# Street_Fighter_v1_0.net
KiCad netlist of a schematic drawn in EAGLE
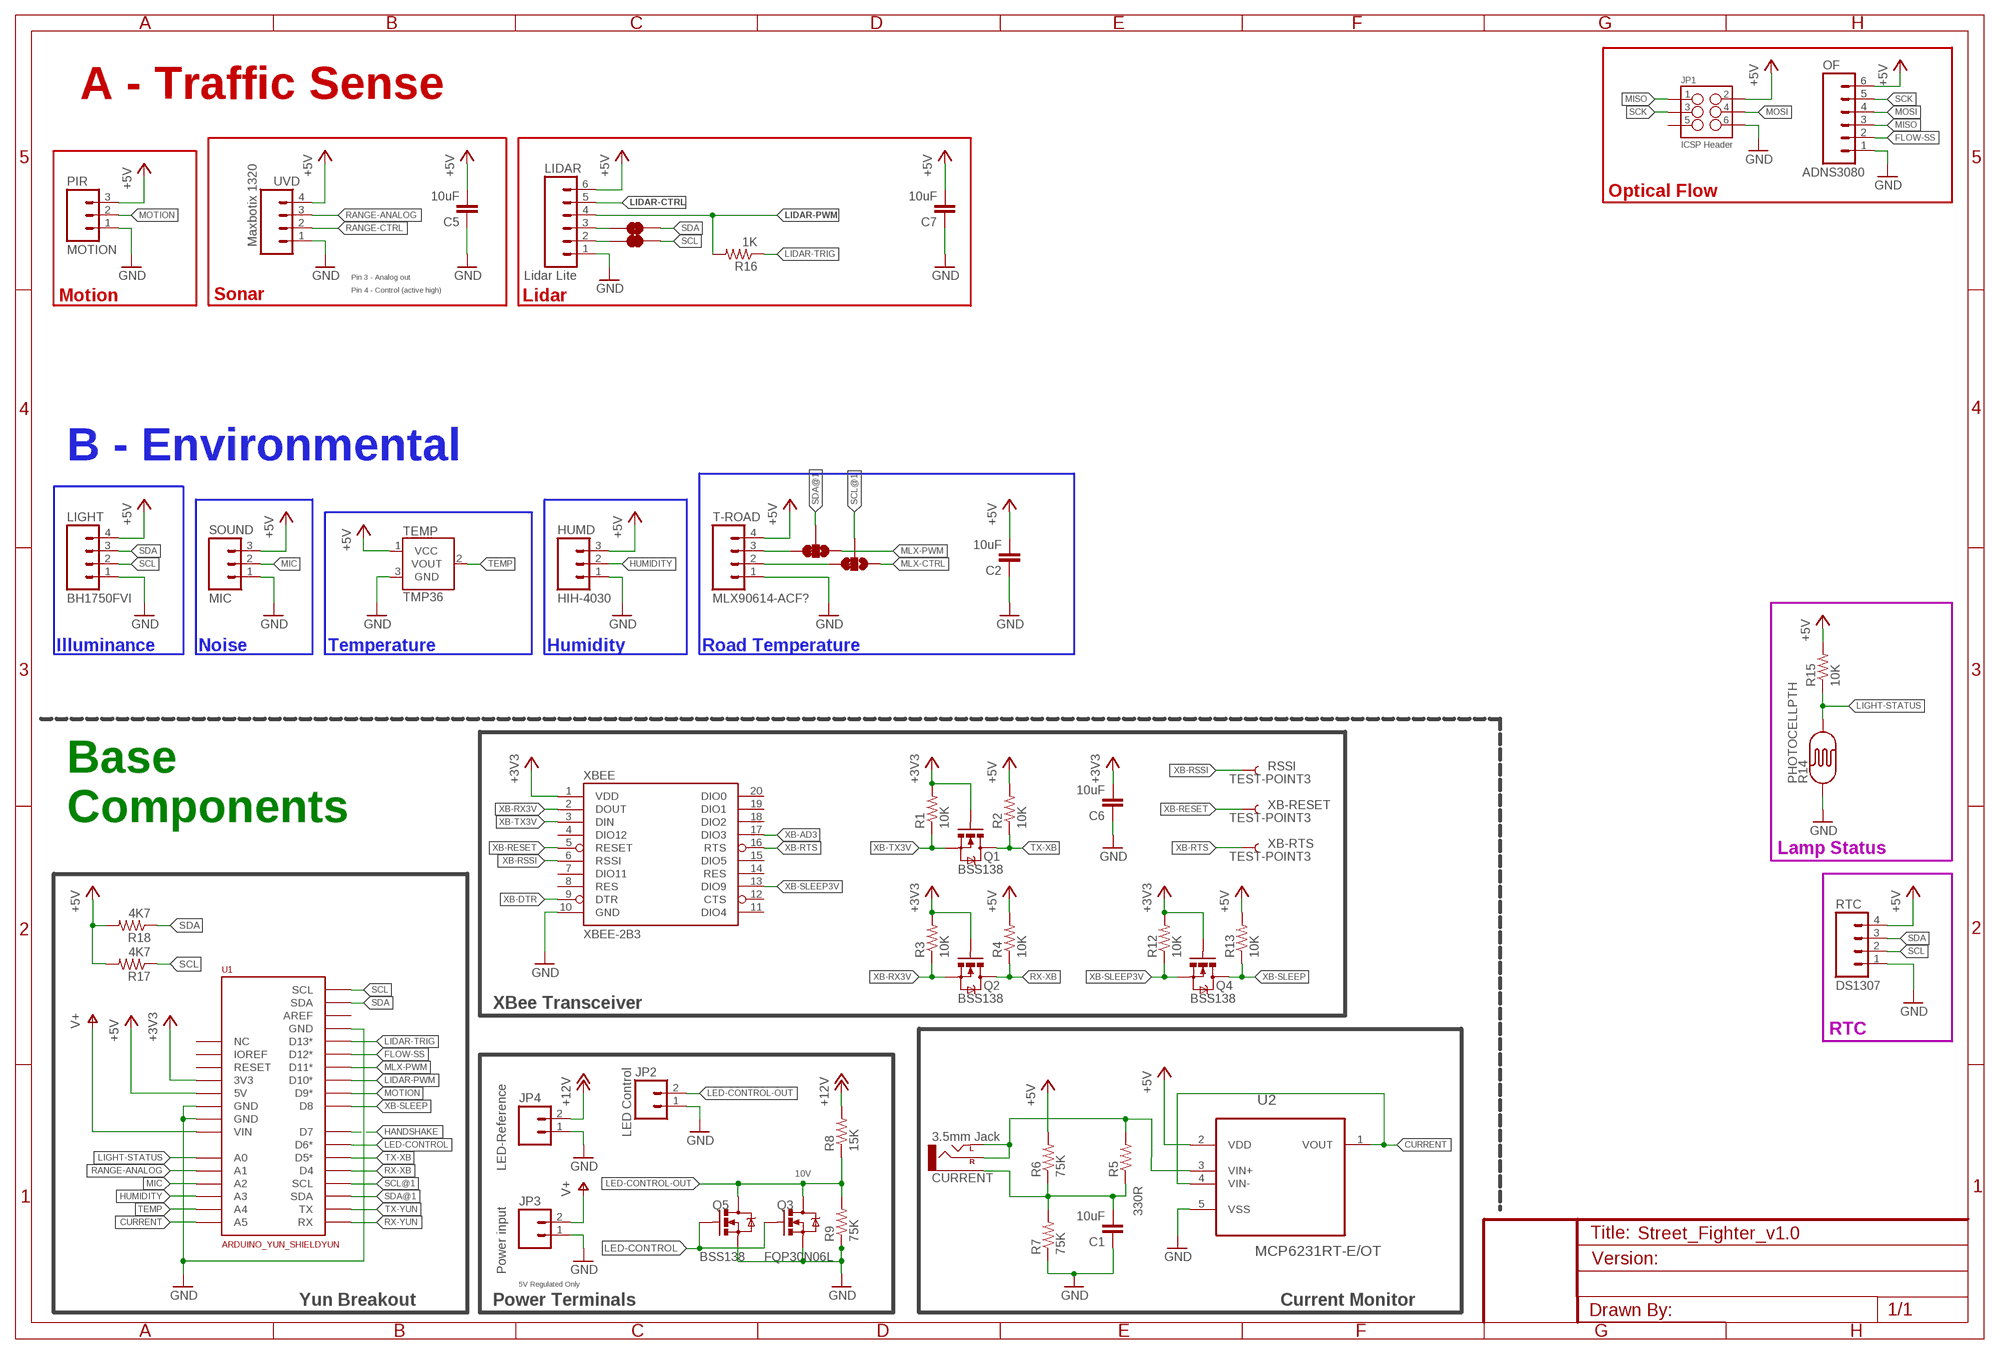
[diagram p0: schematic, sheet 1]

(export (version "E")
  (design (tool "Eeschema 10.0.6"))
  (components
    (comp (ref "C1")
      (value "10uF")
      (footprint "eagle-import:1206")
      (libsource (lib "eagle-import") (part "10UF-6.3V-20%(1206)"))
    )
    (comp (ref "C2")
      (value "10uF")
      (footprint "eagle-import:1206")
      (libsource (lib "eagle-import") (part "10UF-6.3V-20%(1206)"))
    )
    (comp (ref "C5")
      (value "10uF")
      (footprint "eagle-import:1206")
      (libsource (lib "eagle-import") (part "10UF-6.3V-20%(1206)"))
    )
    (comp (ref "C6")
      (value "10uF")
      (footprint "eagle-import:1206")
      (libsource (lib "eagle-import") (part "10UF-6.3V-20%(1206)"))
    )
    (comp (ref "C7")
      (value "10uF")
      (footprint "eagle-import:1206")
      (libsource (lib "eagle-import") (part "10UF-6.3V-20%(1206)"))
    )
    (comp (ref "CURRENT")
      (value "3.5mm Jack")
      (footprint "eagle-import:AUDIO-JACK")
      (libsource (lib "eagle-import") (part "AUDIO-JACKPTH"))
    )
    (comp (ref "HUMD")
      (value "HIH-4030")
      (footprint "eagle-import:1X03")
      (libsource (lib "eagle-import") (part "M03PTH"))
    )
    (comp (ref "JP1")
      (value "ICSP Header")
      (footprint "eagle-import:2X3")
      (libsource (lib "eagle-import") (part "M03X22X3_SILK_SM"))
    )
    (comp (ref "JP2")
      (value "LED Control")
      (footprint "eagle-import:1X02_LONGPADS")
      (libsource (lib "eagle-import") (part "M02PTH3"))
    )
    (comp (ref "JP3")
      (value "Power input")
      (footprint "eagle-import:1X02_LONGPADS")
      (libsource (lib "eagle-import") (part "M02PTH3"))
    )
    (comp (ref "JP4")
      (value "LED-Reference")
      (footprint "eagle-import:1X02_LONGPADS")
      (libsource (lib "eagle-import") (part "M02PTH3"))
    )
    (comp (ref "LIDAR")
      (value "Lidar Lite")
      (footprint "eagle-import:1X06")
      (libsource (lib "eagle-import") (part "M06SIP"))
    )
    (comp (ref "LIGHT")
      (value "BH1750FVI")
      (footprint "eagle-import:1X04")
      (libsource (lib "eagle-import") (part "M04PTH"))
    )
    (comp (ref "OF")
      (value "ADNS3080")
      (footprint "eagle-import:1X06")
      (libsource (lib "eagle-import") (part "M06SIP"))
    )
    (comp (ref "PIR")
      (value "MOTION")
      (footprint "eagle-import:1X03")
      (libsource (lib "eagle-import") (part "M03PTH"))
    )
    (comp (ref "Q1")
      (value "BSS138")
      (footprint "eagle-import:SOT23")
      (libsource (lib "eagle-import") (part "MOSFET-NCHANNELBSS123LT1G"))
    )
    (comp (ref "Q2")
      (value "BSS138")
      (footprint "eagle-import:SOT23")
      (libsource (lib "eagle-import") (part "MOSFET-NCHANNELBSS123LT1G"))
    )
    (comp (ref "Q3")
      (value "FQP30N06L")
      (footprint "eagle-import:TO220V")
      (libsource (lib "eagle-import") (part "MOSFET-NCHANNELFQP30N06L"))
    )
    (comp (ref "Q4")
      (value "BSS138")
      (footprint "eagle-import:SOT23")
      (libsource (lib "eagle-import") (part "MOSFET-NCHANNELBSS123LT1G"))
    )
    (comp (ref "Q5")
      (value "BSS138")
      (footprint "eagle-import:SOT23")
      (libsource (lib "eagle-import") (part "MOSFET-NCHANNELBSS123LT1G"))
    )
    (comp (ref "R1")
      (value "10K")
      (footprint "eagle-import:1206")
      (libsource (lib "eagle-import") (part "RESISTOR1206"))
    )
    (comp (ref "R2")
      (value "10K")
      (footprint "eagle-import:1206")
      (libsource (lib "eagle-import") (part "RESISTOR1206"))
    )
    (comp (ref "R3")
      (value "10K")
      (footprint "eagle-import:1206")
      (libsource (lib "eagle-import") (part "RESISTOR1206"))
    )
    (comp (ref "R4")
      (value "10K")
      (footprint "eagle-import:1206")
      (libsource (lib "eagle-import") (part "RESISTOR1206"))
    )
    (comp (ref "R5")
      (value "330R")
      (footprint "eagle-import:1206")
      (libsource (lib "eagle-import") (part "RESISTOR1206"))
    )
    (comp (ref "R6")
      (value "75K")
      (footprint "eagle-import:1206")
      (libsource (lib "eagle-import") (part "RESISTOR1206"))
    )
    (comp (ref "R7")
      (value "75K")
      (footprint "eagle-import:1206")
      (libsource (lib "eagle-import") (part "RESISTOR1206"))
    )
    (comp (ref "R8")
      (value "15K")
      (footprint "eagle-import:1206")
      (libsource (lib "eagle-import") (part "RESISTOR1206"))
    )
    (comp (ref "R9")
      (value "75K")
      (footprint "eagle-import:1206")
      (libsource (lib "eagle-import") (part "RESISTOR1206"))
    )
    (comp (ref "R12")
      (value "10K")
      (footprint "eagle-import:1206")
      (libsource (lib "eagle-import") (part "RESISTOR1206"))
    )
    (comp (ref "R13")
      (value "10K")
      (footprint "eagle-import:1206")
      (libsource (lib "eagle-import") (part "RESISTOR1206"))
    )
    (comp (ref "R14")
      (value "PHOTOCELLPTH")
      (footprint "eagle-import:PHOTOCELL")
      (libsource (lib "eagle-import") (part "PHOTOCELLPTH"))
    )
    (comp (ref "R15")
      (value "10K")
      (footprint "eagle-import:1206")
      (libsource (lib "eagle-import") (part "RESISTOR1206"))
    )
    (comp (ref "R16")
      (value "1K")
      (footprint "eagle-import:1206")
      (libsource (lib "eagle-import") (part "RESISTOR1206"))
    )
    (comp (ref "R17")
      (value "4K7")
      (footprint "eagle-import:1206")
      (libsource (lib "eagle-import") (part "RESISTOR1206"))
    )
    (comp (ref "R18")
      (value "4K7")
      (footprint "eagle-import:1206")
      (libsource (lib "eagle-import") (part "RESISTOR1206"))
    )
    (comp (ref "RSSI")
      (value "TEST-POINT3")
      (footprint "eagle-import:PAD.03X.03")
      (libsource (lib "eagle-import") (part "TEST-POINT3"))
    )
    (comp (ref "RTC")
      (value "DS1307")
      (footprint "eagle-import:1X04")
      (libsource (lib "eagle-import") (part "M04PTH"))
    )
    (comp (ref "SJ1")
      (value "JUMPER-PAD-2-NC_BY_TRACE")
      (footprint "eagle-import:PAD-JUMPER-2-NC_BY_TRACE_YES_SILK")
      (libsource (lib "eagle-import") (part "JUMPER-PAD-2-NC_BY_TRACE"))
    )
    (comp (ref "SJ2")
      (value "JUMPER-PAD-2-NC_BY_TRACE")
      (footprint "eagle-import:PAD-JUMPER-2-NC_BY_TRACE_YES_SILK")
      (libsource (lib "eagle-import") (part "JUMPER-PAD-2-NC_BY_TRACE"))
    )
    (comp (ref "SJ3")
      (value "JUMPER-PAD-3-2OF3_NC_BY_TRACE_SMALL")
      (footprint "eagle-import:PAD-JUMPER-3-2OF3_NC_BY_TRACE_YES_SILK_FULL_BOX")
      (libsource (lib "eagle-import") (part "JUMPER-PAD-3-2OF3_NC_BY_TRACE_SMALL"))
    )
    (comp (ref "SJ4")
      (value "JUMPER-PAD-3-2OF3_NC_BY_TRACE_SMALL")
      (footprint "eagle-import:PAD-JUMPER-3-2OF3_NC_BY_TRACE_YES_SILK_FULL_BOX")
      (libsource (lib "eagle-import") (part "JUMPER-PAD-3-2OF3_NC_BY_TRACE_SMALL"))
    )
    (comp (ref "SOUND")
      (value "MIC")
      (footprint "eagle-import:1X03")
      (libsource (lib "eagle-import") (part "M03PTH"))
    )
    (comp (ref "T-ROAD")
      (value "MLX90614-ACF?")
      (footprint "eagle-import:1X04")
      (libsource (lib "eagle-import") (part "M04PTH"))
    )
    (comp (ref "TEMP")
      (value "TMP36")
      (footprint "eagle-import:TO-92")
      (libsource (lib "eagle-import") (part "TMP36GT9"))
    )
    (comp (ref "U1")
      (value "ARDUINO_YUN_SHIELDYUN")
      (footprint "eagle-import:DUEMILANOVE_VIAS")
      (libsource (lib "eagle-import") (part "ARDUINO_YUN_SHIELDYUN"))
    )
    (comp (ref "U2")
      (value "MCP6231RT-E/OT")
      (footprint "eagle-import:SOT95P270X145-5N")
      (libsource (lib "eagle-import") (part "MCP6231RT-E/OT"))
    )
    (comp (ref "UVD")
      (value "Maxbotix 1320")
      (footprint "eagle-import:1X04")
      (libsource (lib "eagle-import") (part "M04PTH"))
    )
    (comp (ref "XB-RESET")
      (value "TEST-POINT3")
      (footprint "eagle-import:PAD.03X.03")
      (libsource (lib "eagle-import") (part "TEST-POINT3"))
    )
    (comp (ref "XB-RTS")
      (value "TEST-POINT3")
      (footprint "eagle-import:PAD.03X.03")
      (libsource (lib "eagle-import") (part "TEST-POINT3"))
    )
    (comp (ref "XBEE")
      (value "XBEE-2B3")
      (footprint "eagle-import:XBEE-SMD")
      (libsource (lib "eagle-import") (part "XBEE-2B3"))
    )
  )
  (nets
    (net (code "1") (name "+3V3") (class "Default")
      (node (ref "C6") (pin "2") (pinfunction "2_2") (pintype "passive"))
      (node (ref "Q1") (pin "1") (pinfunction "G_1") (pintype "passive"))
      (node (ref "Q2") (pin "1") (pinfunction "G_1") (pintype "passive"))
      (node (ref "Q4") (pin "1") (pinfunction "G_1") (pintype "passive"))
      (node (ref "R1") (pin "2") (pinfunction "2_2") (pintype "passive"))
      (node (ref "R12") (pin "2") (pinfunction "2_2") (pintype "passive"))
      (node (ref "R3") (pin "2") (pinfunction "2_2") (pintype "passive"))
      (node (ref "U1") (pin "3V3") (pinfunction "3V3_3V3") (pintype "power_in"))
      (node (ref "XBEE") (pin "1") (pinfunction "VDD_1") (pintype "power_in"))
    )
    (net (code "2") (name "+5V") (class "Default")
      (node (ref "C2") (pin "2") (pinfunction "2_2") (pintype "passive"))
      (node (ref "C5") (pin "2") (pinfunction "2_2") (pintype "passive"))
      (node (ref "C7") (pin "2") (pinfunction "2_2") (pintype "passive"))
      (node (ref "HUMD") (pin "3") (pinfunction "3_3") (pintype "passive"))
      (node (ref "JP1") (pin "2") (pinfunction "2_2") (pintype "bidirectional"))
      (node (ref "LIDAR") (pin "6") (pinfunction "6_6") (pintype "passive"))
      (node (ref "LIGHT") (pin "4") (pinfunction "4_4") (pintype "passive"))
      (node (ref "OF") (pin "6") (pinfunction "6_6") (pintype "passive"))
      (node (ref "PIR") (pin "3") (pinfunction "3_3") (pintype "passive"))
      (node (ref "R13") (pin "2") (pinfunction "2_2") (pintype "passive"))
      (node (ref "R15") (pin "2") (pinfunction "2_2") (pintype "passive"))
      (node (ref "R17") (pin "2") (pinfunction "2_2") (pintype "passive"))
      (node (ref "R18") (pin "2") (pinfunction "2_2") (pintype "passive"))
      (node (ref "R2") (pin "2") (pinfunction "2_2") (pintype "passive"))
      (node (ref "R4") (pin "2") (pinfunction "2_2") (pintype "passive"))
      (node (ref "R6") (pin "2") (pinfunction "2_2") (pintype "passive"))
      (node (ref "RTC") (pin "4") (pinfunction "4_4") (pintype "passive"))
      (node (ref "SOUND") (pin "3") (pinfunction "3_3") (pintype "passive"))
      (node (ref "T-ROAD") (pin "4") (pinfunction "4_4") (pintype "passive"))
      (node (ref "TEMP") (pin "1") (pinfunction "VCC_1") (pintype "bidirectional"))
      (node (ref "U1") (pin "5V") (pinfunction "5V_5V") (pintype "power_in"))
      (node (ref "U2") (pin "2") (pinfunction "VDD_2") (pintype "power_in"))
      (node (ref "UVD") (pin "4") (pinfunction "4_4") (pintype "passive"))
    )
    (net (code "3") (name "+12V") (class "Default")
      (node (ref "JP4") (pin "2") (pinfunction "2_2") (pintype "passive"))
      (node (ref "R8") (pin "2") (pinfunction "2_2") (pintype "passive"))
    )
    (net (code "4") (name "CURRENT") (class "Default")
      (node (ref "U1") (pin "A5") (pinfunction "A5_A5") (pintype "bidirectional"))
      (node (ref "U2") (pin "1") (pinfunction "VOUT_1") (pintype "output"))
      (node (ref "U2") (pin "4") (pinfunction "VIN-_4") (pintype "input"))
    )
    (net (code "5") (name "FLOW-SS") (class "Default")
      (node (ref "OF") (pin "2") (pinfunction "2_2") (pintype "passive"))
      (node (ref "U1") (pin "12") (pinfunction "D12*_12") (pintype "bidirectional"))
    )
    (net (code "6") (name "GND") (class "Default")
      (node (ref "C1") (pin "1") (pinfunction "1_1") (pintype "passive"))
      (node (ref "C2") (pin "1") (pinfunction "1_1") (pintype "passive"))
      (node (ref "C5") (pin "1") (pinfunction "1_1") (pintype "passive"))
      (node (ref "C6") (pin "1") (pinfunction "1_1") (pintype "passive"))
      (node (ref "C7") (pin "1") (pinfunction "1_1") (pintype "passive"))
      (node (ref "HUMD") (pin "1") (pinfunction "1_1") (pintype "passive"))
      (node (ref "JP1") (pin "6") (pinfunction "6_6") (pintype "bidirectional"))
      (node (ref "JP2") (pin "1") (pinfunction "1_1") (pintype "passive"))
      (node (ref "JP3") (pin "1") (pinfunction "1_1") (pintype "passive"))
      (node (ref "JP4") (pin "1") (pinfunction "1_1") (pintype "passive"))
      (node (ref "LIDAR") (pin "1") (pinfunction "1_1") (pintype "passive"))
      (node (ref "LIGHT") (pin "1") (pinfunction "1_1") (pintype "passive"))
      (node (ref "OF") (pin "1") (pinfunction "1_1") (pintype "passive"))
      (node (ref "PIR") (pin "1") (pinfunction "1_1") (pintype "passive"))
      (node (ref "Q3") (pin "3") (pinfunction "S_3") (pintype "passive"))
      (node (ref "Q5") (pin "2") (pinfunction "S_2") (pintype "passive"))
      (node (ref "R14") (pin "1") (pinfunction "P$1_1") (pintype "bidirectional"))
      (node (ref "R7") (pin "1") (pinfunction "1_1") (pintype "passive"))
      (node (ref "R9") (pin "1") (pinfunction "1_1") (pintype "passive"))
      (node (ref "RTC") (pin "1") (pinfunction "1_1") (pintype "passive"))
      (node (ref "SOUND") (pin "1") (pinfunction "1_1") (pintype "passive"))
      (node (ref "T-ROAD") (pin "1") (pinfunction "1_1") (pintype "passive"))
      (node (ref "TEMP") (pin "3") (pinfunction "GND_3") (pintype "bidirectional"))
      (node (ref "U1") (pin "GND") (pinfunction "GND_GND") (pintype "power_in"))
      (node (ref "U1") (pin "GND@0") (pinfunction "GND_GND@0") (pintype "power_in"))
      (node (ref "U1") (pin "GND@1") (pinfunction "GND_GND@1") (pintype "power_in"))
      (node (ref "U2") (pin "5") (pinfunction "VSS_5") (pintype "passive"))
      (node (ref "UVD") (pin "1") (pinfunction "1_1") (pintype "passive"))
      (node (ref "XBEE") (pin "10") (pinfunction "GND_10") (pintype "power_in"))
    )
    (net (code "7") (name "HANDSHAKE") (class "Default")
      (node (ref "U1") (pin "7") (pinfunction "D7_7") (pintype "bidirectional"))
    )
    (net (code "8") (name "HUMIDITY") (class "Default")
      (node (ref "HUMD") (pin "2") (pinfunction "2_2") (pintype "passive"))
      (node (ref "U1") (pin "A3") (pinfunction "A3_A3") (pintype "bidirectional"))
    )
    (net (code "9") (name "LED-CONTROL") (class "Default")
      (node (ref "Q3") (pin "1") (pinfunction "G_1") (pintype "passive"))
      (node (ref "Q5") (pin "1") (pinfunction "G_1") (pintype "passive"))
      (node (ref "U1") (pin "6") (pinfunction "D6*_6") (pintype "bidirectional"))
    )
    (net (code "10") (name "LED-CONTROL-OUT") (class "Default")
      (node (ref "JP2") (pin "2") (pinfunction "2_2") (pintype "passive"))
      (node (ref "Q3") (pin "2") (pinfunction "D_2") (pintype "passive"))
      (node (ref "Q5") (pin "3") (pinfunction "D_3") (pintype "passive"))
      (node (ref "R8") (pin "1") (pinfunction "1_1") (pintype "passive"))
      (node (ref "R9") (pin "2") (pinfunction "2_2") (pintype "passive"))
    )
    (net (code "11") (name "LIDAR-CTRL") (class "Default")
      (node (ref "LIDAR") (pin "5") (pinfunction "5_5") (pintype "passive"))
    )
    (net (code "12") (name "LIDAR-PWM") (class "Default")
      (node (ref "LIDAR") (pin "4") (pinfunction "4_4") (pintype "passive"))
      (node (ref "R16") (pin "2") (pinfunction "2_2") (pintype "passive"))
      (node (ref "U1") (pin "10") (pinfunction "D10*_10") (pintype "bidirectional"))
    )
    (net (code "13") (name "LIDAR-TRIG") (class "Default")
      (node (ref "R16") (pin "1") (pinfunction "1_1") (pintype "passive"))
      (node (ref "U1") (pin "13") (pinfunction "D13*_13") (pintype "bidirectional"))
    )
    (net (code "14") (name "LIGHT-STATUS") (class "Default")
      (node (ref "R14") (pin "2") (pinfunction "P$2_2") (pintype "bidirectional"))
      (node (ref "R15") (pin "1") (pinfunction "1_1") (pintype "passive"))
      (node (ref "U1") (pin "A0") (pinfunction "A0_A0") (pintype "bidirectional"))
    )
    (net (code "15") (name "MIC") (class "Default")
      (node (ref "SOUND") (pin "2") (pinfunction "2_2") (pintype "passive"))
      (node (ref "U1") (pin "A2") (pinfunction "A2_A2") (pintype "bidirectional"))
    )
    (net (code "16") (name "MISO") (class "Default")
      (node (ref "JP1") (pin "1") (pinfunction "1_1") (pintype "bidirectional"))
      (node (ref "OF") (pin "3") (pinfunction "3_3") (pintype "passive"))
    )
    (net (code "17") (name "MLX-CTRL") (class "Default")
      (node (ref "SJ4") (pin "1") (pinfunction "1_1") (pintype "passive"))
    )
    (net (code "18") (name "MLX-PWM") (class "Default")
      (node (ref "SJ3") (pin "1") (pinfunction "1_1") (pintype "passive"))
      (node (ref "U1") (pin "11") (pinfunction "D11*_11") (pintype "bidirectional"))
    )
    (net (code "19") (name "MOSI") (class "Default")
      (node (ref "JP1") (pin "4") (pinfunction "4_4") (pintype "bidirectional"))
      (node (ref "OF") (pin "4") (pinfunction "4_4") (pintype "passive"))
    )
    (net (code "20") (name "MOTION") (class "Default")
      (node (ref "PIR") (pin "2") (pinfunction "2_2") (pintype "passive"))
      (node (ref "U1") (pin "9") (pinfunction "D9*_9") (pintype "bidirectional"))
    )
    (net (code "21") (name "Net-(C1-Pad2)") (class "Default")
      (node (ref "C1") (pin "2") (pinfunction "2_2") (pintype "passive"))
      (node (ref "CURRENT") (pin "SLEEVE") (pinfunction "SLEEVE_SLEEVE") (pintype "bidirectional"))
      (node (ref "R5") (pin "1") (pinfunction "1_1") (pintype "passive"))
      (node (ref "R6") (pin "1") (pinfunction "1_1") (pintype "passive"))
      (node (ref "R7") (pin "2") (pinfunction "2_2") (pintype "passive"))
    )
    (net (code "22") (name "Net-(CURRENT-LEFT)") (class "Default")
      (node (ref "CURRENT") (pin "RING") (pinfunction "RIGHT_RING") (pintype "bidirectional"))
      (node (ref "CURRENT") (pin "TIP") (pinfunction "LEFT_TIP") (pintype "bidirectional"))
      (node (ref "R5") (pin "2") (pinfunction "2_2") (pintype "passive"))
      (node (ref "U2") (pin "3") (pinfunction "VIN+_3") (pintype "input"))
    )
    (net (code "23") (name "RANGE-ANALOG") (class "Default")
      (node (ref "U1") (pin "A1") (pinfunction "A1_A1") (pintype "bidirectional"))
      (node (ref "UVD") (pin "3") (pinfunction "3_3") (pintype "passive"))
    )
    (net (code "24") (name "RANGE-CTRL") (class "Default")
      (node (ref "UVD") (pin "2") (pinfunction "2_2") (pintype "passive"))
    )
    (net (code "25") (name "RX-XB") (class "Default")
      (node (ref "Q2") (pin "3") (pinfunction "D_3") (pintype "passive"))
      (node (ref "R4") (pin "1") (pinfunction "1_1") (pintype "passive"))
      (node (ref "U1") (pin "D4") (pinfunction "D4_D4") (pintype "bidirectional"))
    )
    (net (code "26") (name "RX-YUN") (class "Default")
      (node (ref "U1") (pin "0") (pinfunction "RX_0") (pintype "bidirectional"))
    )
    (net (code "27") (name "SCK") (class "Default")
      (node (ref "JP1") (pin "3") (pinfunction "3_3") (pintype "bidirectional"))
      (node (ref "OF") (pin "5") (pinfunction "5_5") (pintype "passive"))
    )
    (net (code "28") (name "SCL") (class "Default")
      (node (ref "LIDAR") (pin "2") (pinfunction "2_2") (pintype "passive"))
      (node (ref "LIGHT") (pin "2") (pinfunction "2_2") (pintype "passive"))
      (node (ref "R17") (pin "1") (pinfunction "1_1") (pintype "passive"))
      (node (ref "RTC") (pin "2") (pinfunction "2_2") (pintype "passive"))
      (node (ref "SJ2") (pin "1") (pinfunction "1_1") (pintype "passive"))
      (node (ref "SJ2") (pin "2") (pinfunction "2_2") (pintype "passive"))
      (node (ref "U1") (pin "3@1") (pinfunction "SCL_3@1") (pintype "bidirectional"))
    )
    (net (code "29") (name "SCL@1") (class "Default")
      (node (ref "SJ4") (pin "2") (pinfunction "2_2") (pintype "passive"))
      (node (ref "SJ4") (pin "3") (pinfunction "3_3") (pintype "passive"))
      (node (ref "T-ROAD") (pin "2") (pinfunction "2_2") (pintype "passive"))
      (node (ref "U1") (pin "3") (pinfunction "SCL_3") (pintype "bidirectional"))
    )
    (net (code "30") (name "SDA") (class "Default")
      (node (ref "LIDAR") (pin "3") (pinfunction "3_3") (pintype "passive"))
      (node (ref "LIGHT") (pin "3") (pinfunction "3_3") (pintype "passive"))
      (node (ref "R18") (pin "1") (pinfunction "1_1") (pintype "passive"))
      (node (ref "RTC") (pin "3") (pinfunction "3_3") (pintype "passive"))
      (node (ref "SJ1") (pin "1") (pinfunction "1_1") (pintype "passive"))
      (node (ref "SJ1") (pin "2") (pinfunction "2_2") (pintype "passive"))
      (node (ref "U1") (pin "2@1") (pinfunction "SDA_2@1") (pintype "bidirectional"))
    )
    (net (code "31") (name "SDA@1") (class "Default")
      (node (ref "SJ3") (pin "2") (pinfunction "2_2") (pintype "passive"))
      (node (ref "SJ3") (pin "3") (pinfunction "3_3") (pintype "passive"))
      (node (ref "T-ROAD") (pin "3") (pinfunction "3_3") (pintype "passive"))
      (node (ref "U1") (pin "2") (pinfunction "SDA_2") (pintype "bidirectional"))
    )
    (net (code "32") (name "TEMP") (class "Default")
      (node (ref "TEMP") (pin "2") (pinfunction "VOUT_2") (pintype "bidirectional"))
      (node (ref "U1") (pin "A4") (pinfunction "A4_A4") (pintype "bidirectional"))
    )
    (net (code "33") (name "TX-XB") (class "Default")
      (node (ref "Q1") (pin "3") (pinfunction "D_3") (pintype "passive"))
      (node (ref "R2") (pin "1") (pinfunction "1_1") (pintype "passive"))
      (node (ref "U1") (pin "5") (pinfunction "D5*_5") (pintype "bidirectional"))
    )
    (net (code "34") (name "TX-YUN") (class "Default")
      (node (ref "U1") (pin "1") (pinfunction "TX_1") (pintype "bidirectional"))
    )
    (net (code "35") (name "V+") (class "Default")
      (node (ref "JP3") (pin "2") (pinfunction "2_2") (pintype "passive"))
      (node (ref "U1") (pin "VIN") (pinfunction "VIN_VIN") (pintype "power_in"))
    )
    (net (code "36") (name "XB-AD3") (class "Default")
      (node (ref "XBEE") (pin "17") (pinfunction "DIO3_17") (pintype "bidirectional"))
    )
    (net (code "37") (name "XB-DTR") (class "Default")
      (node (ref "XBEE") (pin "9") (pinfunction "DTR_9") (pintype "bidirectional"))
    )
    (net (code "38") (name "XB-RESET") (class "Default")
      (node (ref "XB-RESET") (pin "P$1") (pinfunction "1_P$1") (pintype "bidirectional"))
      (node (ref "XBEE") (pin "5") (pinfunction "RESET_5") (pintype "input"))
    )
    (net (code "39") (name "XB-RSSI") (class "Default")
      (node (ref "RSSI") (pin "P$1") (pinfunction "1_P$1") (pintype "bidirectional"))
      (node (ref "XBEE") (pin "6") (pinfunction "RSSI_6") (pintype "bidirectional"))
    )
    (net (code "40") (name "XB-RTS") (class "Default")
      (node (ref "XB-RTS") (pin "P$1") (pinfunction "1_P$1") (pintype "bidirectional"))
      (node (ref "XBEE") (pin "16") (pinfunction "RTS_16") (pintype "input"))
    )
    (net (code "41") (name "XB-RX3V") (class "Default")
      (node (ref "Q2") (pin "2") (pinfunction "S_2") (pintype "passive"))
      (node (ref "R3") (pin "1") (pinfunction "1_1") (pintype "passive"))
      (node (ref "XBEE") (pin "2") (pinfunction "DOUT_2") (pintype "output"))
    )
    (net (code "42") (name "XB-SLEEP") (class "Default")
      (node (ref "Q4") (pin "3") (pinfunction "D_3") (pintype "passive"))
      (node (ref "R13") (pin "1") (pinfunction "1_1") (pintype "passive"))
      (node (ref "U1") (pin "8") (pinfunction "D8_8") (pintype "bidirectional"))
    )
    (net (code "43") (name "XB-SLEEP3V") (class "Default")
      (node (ref "Q4") (pin "2") (pinfunction "S_2") (pintype "passive"))
      (node (ref "R12") (pin "1") (pinfunction "1_1") (pintype "passive"))
      (node (ref "XBEE") (pin "13") (pinfunction "DIO9_13") (pintype "bidirectional"))
    )
    (net (code "44") (name "XB-TX3V") (class "Default")
      (node (ref "Q1") (pin "2") (pinfunction "S_2") (pintype "passive"))
      (node (ref "R1") (pin "1") (pinfunction "1_1") (pintype "passive"))
      (node (ref "XBEE") (pin "3") (pinfunction "DIN_3") (pintype "input"))
    )
    (net (code "45") (name "unconnected-(JP1-Pad5)") (class "Default")
      (node (ref "JP1") (pin "5") (pinfunction "5_5") (pintype "bidirectional"))
    )
    (net (code "46") (name "unconnected-(U1-PadAREF)") (class "Default")
      (node (ref "U1") (pin "AREF") (pinfunction "AREF_AREF") (pintype "bidirectional"))
    )
    (net (code "47") (name "unconnected-(U1-PadIOREF)") (class "Default")
      (node (ref "U1") (pin "IOREF") (pinfunction "IOREF_IOREF") (pintype "bidirectional"))
    )
    (net (code "48") (name "unconnected-(U1-PadNC)") (class "Default")
      (node (ref "U1") (pin "NC") (pinfunction "NC_NC") (pintype "no_connect"))
    )
    (net (code "49") (name "unconnected-(U1-PadRESET)") (class "Default")
      (node (ref "U1") (pin "RESET") (pinfunction "RESET_RESET") (pintype "bidirectional"))
    )
    (net (code "50") (name "unconnected-(XBEE-CTS-Pad12)") (class "Default")
      (node (ref "XBEE") (pin "12") (pinfunction "CTS_12") (pintype "output"))
    )
    (net (code "51") (name "unconnected-(XBEE-DIO0-Pad20)") (class "Default")
      (node (ref "XBEE") (pin "20") (pinfunction "DIO0_20") (pintype "bidirectional"))
    )
    (net (code "52") (name "unconnected-(XBEE-DIO1-Pad19)") (class "Default")
      (node (ref "XBEE") (pin "19") (pinfunction "DIO1_19") (pintype "bidirectional"))
    )
    (net (code "53") (name "unconnected-(XBEE-DIO2-Pad18)") (class "Default")
      (node (ref "XBEE") (pin "18") (pinfunction "DIO2_18") (pintype "bidirectional"))
    )
    (net (code "54") (name "unconnected-(XBEE-DIO4-Pad11)") (class "Default")
      (node (ref "XBEE") (pin "11") (pinfunction "DIO4_11") (pintype "bidirectional"))
    )
    (net (code "55") (name "unconnected-(XBEE-DIO5-Pad15)") (class "Default")
      (node (ref "XBEE") (pin "15") (pinfunction "DIO5_15") (pintype "bidirectional"))
    )
    (net (code "56") (name "unconnected-(XBEE-DIO11-Pad7)") (class "Default")
      (node (ref "XBEE") (pin "7") (pinfunction "DIO11_7") (pintype "bidirectional"))
    )
    (net (code "57") (name "unconnected-(XBEE-DIO12-Pad4)") (class "Default")
      (node (ref "XBEE") (pin "4") (pinfunction "DIO12_4") (pintype "bidirectional"))
    )
    (net (code "58") (name "unconnected-(XBEE-RES-Pad8)") (class "Default")
      (node (ref "XBEE") (pin "8") (pinfunction "RES_8") (pintype "bidirectional"))
    )
    (net (code "59") (name "unconnected-(XBEE-RES-Pad14)") (class "Default")
      (node (ref "XBEE") (pin "14") (pinfunction "RES_14") (pintype "bidirectional"))
    )
  )
)
